# Mixer.net
KiCad netlist of a schematic drawn in Altium Designer
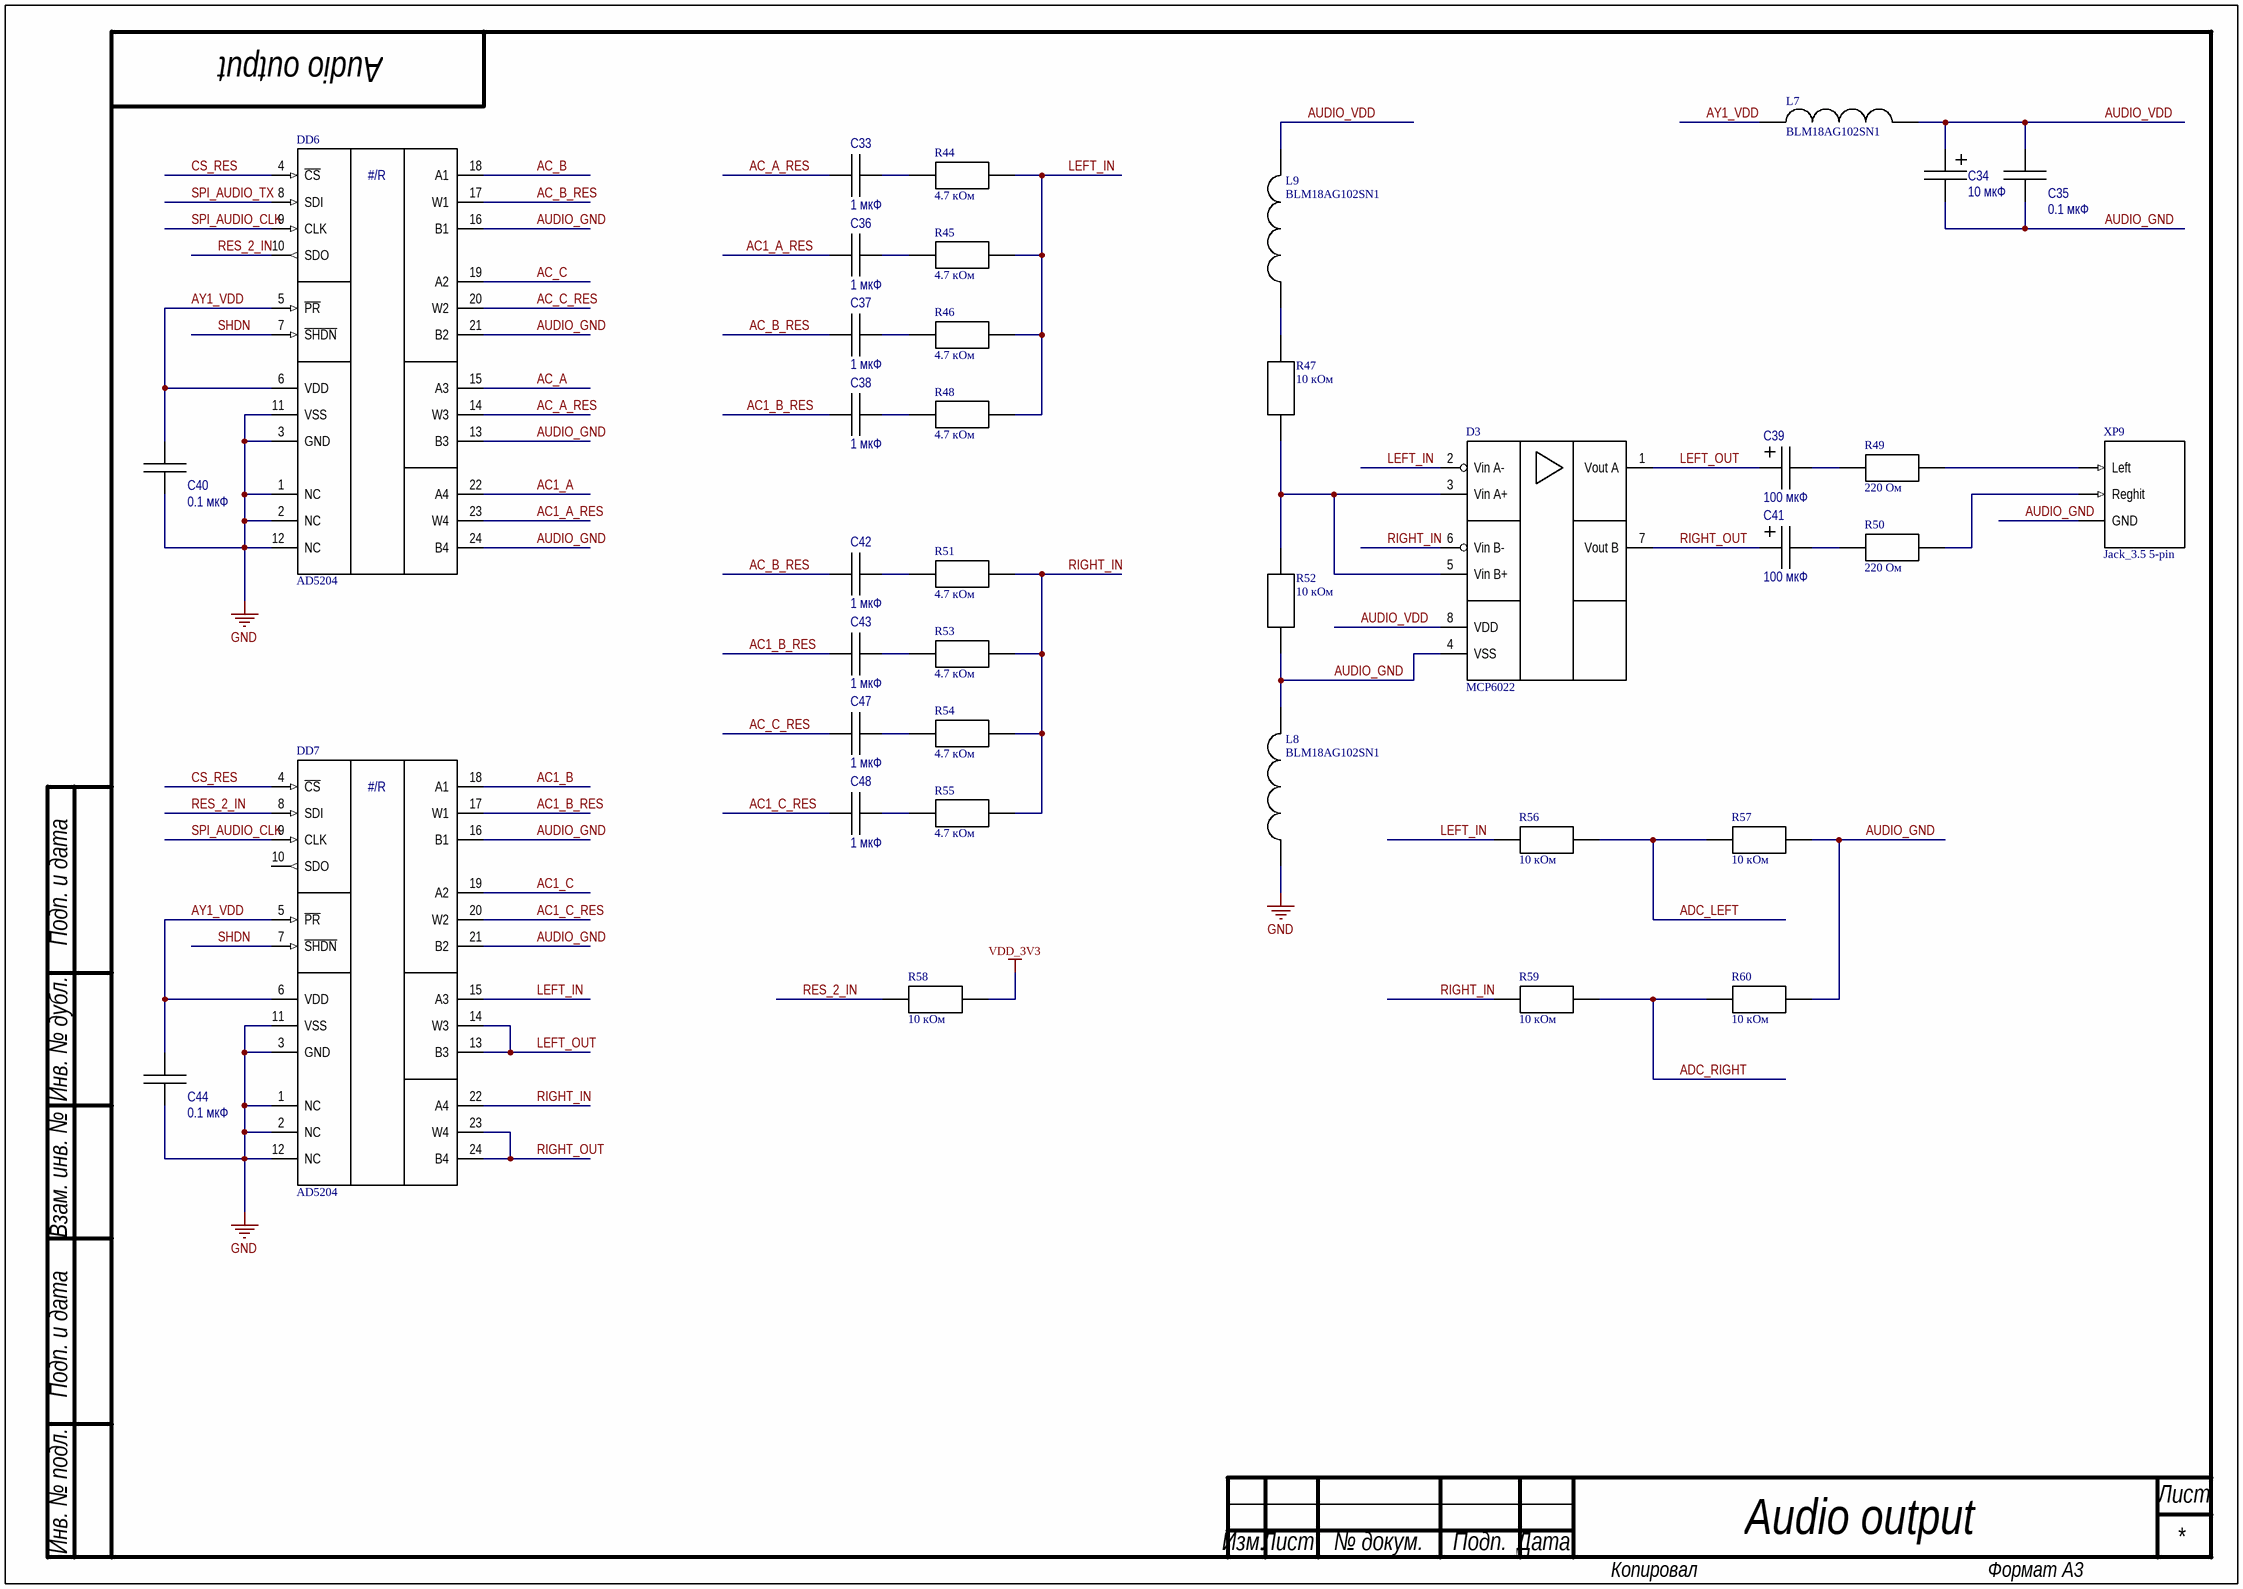
[diagram p0: Mixer.SchDoc]

(export (version "E")
  (design (tool "Eeschema 10.0.6"))
  (components
    (comp (ref "C33")
      (value "1 мкФ")
      (footprint "C 1206")
      (description "SMD Capacitor 1206")
      (fields
        (field (name "TOLERANCE") "/Укажите допуск в процентах/")
        (field (name "MANUFACTURER") "/Укажите компанию-производителя/")
      )
      (libsource (lib "my_lib") (part "CAP 1206"))
    )
    (comp (ref "C34")
      (value "10 мкФ")
      (footprint "C TAN_C")
      (description "SMD Tantalium Capacitor C")
      (fields
        (field (name "TOLERANCE") "/Укажите допуск в процентах/")
        (field (name "MANUFACTURER") "/Укажите компанию-производителя/")
      )
      (libsource (lib "my_lib") (part "CAP TAN_C"))
    )
    (comp (ref "C35")
      (value "0.1 мкФ")
      (footprint "C 1206")
      (description "SMD Capacitor 1206")
      (fields
        (field (name "TOLERANCE") "/Укажите допуск в процентах/")
        (field (name "MANUFACTURER") "/Укажите компанию-производителя/")
      )
      (libsource (lib "my_lib") (part "CAP 1206"))
    )
    (comp (ref "C36")
      (value "1 мкФ")
      (footprint "C 1206")
      (description "SMD Capacitor 1206")
      (fields
        (field (name "TOLERANCE") "/Укажите допуск в процентах/")
        (field (name "MANUFACTURER") "/Укажите компанию-производителя/")
      )
      (libsource (lib "my_lib") (part "CAP 1206"))
    )
    (comp (ref "C37")
      (value "1 мкФ")
      (footprint "C 1206")
      (description "SMD Capacitor 1206")
      (fields
        (field (name "TOLERANCE") "/Укажите допуск в процентах/")
        (field (name "MANUFACTURER") "/Укажите компанию-производителя/")
      )
      (libsource (lib "my_lib") (part "CAP 1206"))
    )
    (comp (ref "C38")
      (value "1 мкФ")
      (footprint "C 1206")
      (description "SMD Capacitor 1206")
      (fields
        (field (name "TOLERANCE") "/Укажите допуск в процентах/")
        (field (name "MANUFACTURER") "/Укажите компанию-производителя/")
      )
      (libsource (lib "my_lib") (part "CAP 1206"))
    )
    (comp (ref "C39")
      (value "100 мкФ")
      (footprint "C TAN_D")
      (description "SMD Tantalium Capacitor D")
      (fields
        (field (name "TOLERANCE") "/Укажите допуск в процентах/")
        (field (name "MANUFACTURER") "/Укажите компанию-производителя/")
      )
      (libsource (lib "my_lib") (part "CAP TAN_D"))
    )
    (comp (ref "C40")
      (value "0.1 мкФ")
      (footprint "C 1206")
      (description "SMD Capacitor 1206")
      (fields
        (field (name "TOLERANCE") "/Укажите допуск в процентах/")
        (field (name "MANUFACTURER") "/Укажите компанию-производителя/")
      )
      (libsource (lib "my_lib") (part "CAP 1206"))
    )
    (comp (ref "C41")
      (value "100 мкФ")
      (footprint "C TAN_D")
      (description "SMD Tantalium Capacitor D")
      (fields
        (field (name "TOLERANCE") "/Укажите допуск в процентах/")
        (field (name "MANUFACTURER") "/Укажите компанию-производителя/")
      )
      (libsource (lib "my_lib") (part "CAP TAN_D"))
    )
    (comp (ref "C42")
      (value "1 мкФ")
      (footprint "C 1206")
      (description "SMD Capacitor 1206")
      (fields
        (field (name "TOLERANCE") "/Укажите допуск в процентах/")
        (field (name "MANUFACTURER") "/Укажите компанию-производителя/")
      )
      (libsource (lib "my_lib") (part "CAP 1206"))
    )
    (comp (ref "C43")
      (value "1 мкФ")
      (footprint "C 1206")
      (description "SMD Capacitor 1206")
      (fields
        (field (name "TOLERANCE") "/Укажите допуск в процентах/")
        (field (name "MANUFACTURER") "/Укажите компанию-производителя/")
      )
      (libsource (lib "my_lib") (part "CAP 1206"))
    )
    (comp (ref "C44")
      (value "0.1 мкФ")
      (footprint "C 1206")
      (description "SMD Capacitor 1206")
      (fields
        (field (name "TOLERANCE") "/Укажите допуск в процентах/")
        (field (name "MANUFACTURER") "/Укажите компанию-производителя/")
      )
      (libsource (lib "my_lib") (part "CAP 1206"))
    )
    (comp (ref "C47")
      (value "1 мкФ")
      (footprint "C 1206")
      (description "SMD Capacitor 1206")
      (fields
        (field (name "TOLERANCE") "/Укажите допуск в процентах/")
        (field (name "MANUFACTURER") "/Укажите компанию-производителя/")
      )
      (libsource (lib "my_lib") (part "CAP 1206"))
    )
    (comp (ref "C48")
      (value "1 мкФ")
      (footprint "C 1206")
      (description "SMD Capacitor 1206")
      (fields
        (field (name "TOLERANCE") "/Укажите допуск в процентах/")
        (field (name "MANUFACTURER") "/Укажите компанию-производителя/")
      )
      (libsource (lib "my_lib") (part "CAP 1206"))
    )
    (comp (ref "D3") (value "MCP6022") (footprint "SOIC-8") (libsource (lib "my_lib") (part "MCP6022")))
    (comp (ref "DD6") (value "AD5204") (footprint "TSSOP-24") (libsource (lib "my_lib") (part "AD5204")))
    (comp (ref "DD7") (value "AD5204") (footprint "TSSOP-24") (libsource (lib "my_lib") (part "AD5204")))
    (comp (ref "L7")
      (value "BLM18AG102SN1")
      (footprint "FB 0603")
      (libsource (lib "my_lib") (part "BLM18AG102SN1"))
    )
    (comp (ref "L8")
      (value "BLM18AG102SN1")
      (footprint "FB 0603")
      (libsource (lib "my_lib") (part "BLM18AG102SN1"))
    )
    (comp (ref "L9")
      (value "BLM18AG102SN1")
      (footprint "FB 0603")
      (libsource (lib "my_lib") (part "BLM18AG102SN1"))
    )
    (comp (ref "R44") (value "4.7 кОм") (footprint "RES 0805") (libsource (lib "my_lib") (part "RES 0805")))
    (comp (ref "R45") (value "4.7 кОм") (footprint "RES 0805") (libsource (lib "my_lib") (part "RES 0805")))
    (comp (ref "R46") (value "4.7 кОм") (footprint "RES 0805") (libsource (lib "my_lib") (part "RES 0805")))
    (comp (ref "R47") (value "10 кОм") (footprint "RES 0805") (libsource (lib "my_lib") (part "RES 0805")))
    (comp (ref "R48") (value "4.7 кОм") (footprint "RES 0805") (libsource (lib "my_lib") (part "RES 0805")))
    (comp (ref "R49") (value "220 Ом") (footprint "RES 0805") (libsource (lib "my_lib") (part "RES 0805")))
    (comp (ref "R50") (value "220 Ом") (footprint "RES 0805") (libsource (lib "my_lib") (part "RES 0805")))
    (comp (ref "R51") (value "4.7 кОм") (footprint "RES 0805") (libsource (lib "my_lib") (part "RES 0805")))
    (comp (ref "R52") (value "10 кОм") (footprint "RES 0805") (libsource (lib "my_lib") (part "RES 0805")))
    (comp (ref "R53") (value "4.7 кОм") (footprint "RES 0805") (libsource (lib "my_lib") (part "RES 0805")))
    (comp (ref "R54") (value "4.7 кОм") (footprint "RES 0805") (libsource (lib "my_lib") (part "RES 0805")))
    (comp (ref "R55") (value "4.7 кОм") (footprint "RES 0805") (libsource (lib "my_lib") (part "RES 0805")))
    (comp (ref "R56") (value "10 кОм") (footprint "RES 0805") (libsource (lib "my_lib") (part "RES 0805")))
    (comp (ref "R57") (value "10 кОм") (footprint "RES 0805") (libsource (lib "my_lib") (part "RES 0805")))
    (comp (ref "R58") (value "10 кОм") (footprint "RES 0805") (libsource (lib "my_lib") (part "RES 0805")))
    (comp (ref "R59") (value "10 кОм") (footprint "RES 0805") (libsource (lib "my_lib") (part "RES 0805")))
    (comp (ref "R60") (value "10 кОм") (footprint "RES 0805") (libsource (lib "my_lib") (part "RES 0805")))
    (comp (ref "XP9")
      (value "Jack_3.5 5-pin")
      (footprint "JACK 3.5  female")
      (libsource (lib "my_lib") (part "Jack_3.5 5-pin"))
    )
  )
  (nets
    (net (code "1") (name "/AC1_A") (class "Default")
      (node (ref "DD6") (pin "22") (pinfunction "A4_22") (pintype "passive"))
    )
    (net (code "2") (name "/AC1_A_RES") (class "Default")
      (node (ref "C36") (pin "1") (pinfunction "1_1") (pintype "passive"))
      (node (ref "DD6") (pin "23") (pinfunction "W4_23") (pintype "passive"))
    )
    (net (code "3") (name "/AC1_B") (class "Default")
      (node (ref "DD7") (pin "18") (pinfunction "A1_18") (pintype "passive"))
    )
    (net (code "4") (name "/AC1_B_RES") (class "Default")
      (node (ref "C38") (pin "1") (pinfunction "1_1") (pintype "passive"))
      (node (ref "C43") (pin "1") (pinfunction "1_1") (pintype "passive"))
      (node (ref "DD7") (pin "17") (pinfunction "W1_17") (pintype "passive"))
    )
    (net (code "5") (name "/AC1_C") (class "Default")
      (node (ref "DD7") (pin "19") (pinfunction "A2_19") (pintype "passive"))
    )
    (net (code "6") (name "/AC1_C_RES") (class "Default")
      (node (ref "C48") (pin "1") (pinfunction "1_1") (pintype "passive"))
      (node (ref "DD7") (pin "20") (pinfunction "W2_20") (pintype "passive"))
    )
    (net (code "7") (name "/AC_A") (class "Default")
      (node (ref "DD6") (pin "15") (pinfunction "A3_15") (pintype "passive"))
    )
    (net (code "8") (name "/AC_A_RES") (class "Default")
      (node (ref "C33") (pin "1") (pinfunction "1_1") (pintype "passive"))
      (node (ref "DD6") (pin "14") (pinfunction "W3_14") (pintype "passive"))
    )
    (net (code "9") (name "/AC_B") (class "Default")
      (node (ref "DD6") (pin "18") (pinfunction "A1_18") (pintype "passive"))
    )
    (net (code "10") (name "/AC_B_RES") (class "Default")
      (node (ref "C37") (pin "1") (pinfunction "1_1") (pintype "passive"))
      (node (ref "C42") (pin "1") (pinfunction "1_1") (pintype "passive"))
      (node (ref "DD6") (pin "17") (pinfunction "W1_17") (pintype "passive"))
    )
    (net (code "11") (name "/AC_C") (class "Default")
      (node (ref "DD6") (pin "19") (pinfunction "A2_19") (pintype "passive"))
    )
    (net (code "12") (name "/AC_C_RES") (class "Default")
      (node (ref "C47") (pin "1") (pinfunction "1_1") (pintype "passive"))
      (node (ref "DD6") (pin "20") (pinfunction "W2_20") (pintype "passive"))
    )
    (net (code "13") (name "/ADC_LEFT") (class "Default")
      (node (ref "R56") (pin "1") (pinfunction "1_1") (pintype "passive"))
      (node (ref "R57") (pin "2") (pinfunction "2_2") (pintype "passive"))
    )
    (net (code "14") (name "/ADC_RIGHT") (class "Default")
      (node (ref "R59") (pin "1") (pinfunction "1_1") (pintype "passive"))
      (node (ref "R60") (pin "2") (pinfunction "2_2") (pintype "passive"))
    )
    (net (code "15") (name "/AUDIO_GND") (class "Default")
      (node (ref "C34") (pin "2") (pinfunction "2_2") (pintype "passive"))
      (node (ref "C35") (pin "2") (pinfunction "2_2") (pintype "passive"))
      (node (ref "D3") (pin "4") (pinfunction "VSS_4") (pintype "power_in"))
      (node (ref "DD6") (pin "13") (pinfunction "B3_13") (pintype "passive"))
      (node (ref "DD6") (pin "16") (pinfunction "B1_16") (pintype "passive"))
      (node (ref "DD6") (pin "21") (pinfunction "B2_21") (pintype "passive"))
      (node (ref "DD6") (pin "24") (pinfunction "B4_24") (pintype "passive"))
      (node (ref "DD7") (pin "16") (pinfunction "B1_16") (pintype "passive"))
      (node (ref "DD7") (pin "21") (pinfunction "B2_21") (pintype "passive"))
      (node (ref "L8") (pin "2") (pinfunction "2_2") (pintype "passive"))
      (node (ref "R52") (pin "1") (pinfunction "1_1") (pintype "passive"))
      (node (ref "R57") (pin "1") (pinfunction "1_1") (pintype "passive"))
      (node (ref "R60") (pin "1") (pinfunction "1_1") (pintype "passive"))
      (node (ref "XP9") (pin "G") (pinfunction "GND_G") (pintype "power_in"))
    )
    (net (code "16") (name "/AUDIO_VDD") (class "Default")
      (node (ref "C34") (pin "1") (pinfunction "1_1") (pintype "passive"))
      (node (ref "C35") (pin "1") (pinfunction "1_1") (pintype "passive"))
      (node (ref "D3") (pin "8") (pinfunction "VDD_8") (pintype "power_in"))
      (node (ref "L7") (pin "2") (pinfunction "2_2") (pintype "passive"))
      (node (ref "L9") (pin "2") (pinfunction "2_2") (pintype "passive"))
    )
    (net (code "17") (name "/AY1_VDD") (class "Default")
      (node (ref "C40") (pin "1") (pinfunction "1_1") (pintype "passive"))
      (node (ref "C44") (pin "1") (pinfunction "1_1") (pintype "passive"))
      (node (ref "DD6") (pin "5") (pinfunction "~{PR}_5") (pintype "input"))
      (node (ref "DD6") (pin "6") (pinfunction "VDD_6") (pintype "power_in"))
      (node (ref "DD7") (pin "5") (pinfunction "~{PR}_5") (pintype "input"))
      (node (ref "DD7") (pin "6") (pinfunction "VDD_6") (pintype "power_in"))
      (node (ref "L7") (pin "1") (pinfunction "1_1") (pintype "passive"))
    )
    (net (code "18") (name "/CS_RES") (class "Default")
      (node (ref "DD6") (pin "4") (pinfunction "~{CS}_4") (pintype "input"))
      (node (ref "DD7") (pin "4") (pinfunction "~{CS}_4") (pintype "input"))
    )
    (net (code "19") (name "/LEFT_IN") (class "Default")
      (node (ref "D3") (pin "2") (pinfunction "Vin_A-_2") (pintype "passive"))
      (node (ref "DD7") (pin "15") (pinfunction "A3_15") (pintype "passive"))
      (node (ref "R44") (pin "2") (pinfunction "2_2") (pintype "passive"))
      (node (ref "R45") (pin "2") (pinfunction "2_2") (pintype "passive"))
      (node (ref "R46") (pin "2") (pinfunction "2_2") (pintype "passive"))
      (node (ref "R48") (pin "2") (pinfunction "2_2") (pintype "passive"))
      (node (ref "R56") (pin "2") (pinfunction "2_2") (pintype "passive"))
    )
    (net (code "20") (name "/LEFT_OUT") (class "Default")
      (node (ref "C39") (pin "1") (pinfunction "1_1") (pintype "passive"))
      (node (ref "D3") (pin "1") (pinfunction "Vout_A_1") (pintype "passive"))
      (node (ref "DD7") (pin "13") (pinfunction "B3_13") (pintype "passive"))
      (node (ref "DD7") (pin "14") (pinfunction "W3_14") (pintype "passive"))
    )
    (net (code "21") (name "/RES_2_IN") (class "Default")
      (node (ref "DD6") (pin "10") (pinfunction "SDO_10") (pintype "output"))
      (node (ref "DD7") (pin "8") (pinfunction "SDI_8") (pintype "input"))
      (node (ref "R58") (pin "1") (pinfunction "1_1") (pintype "passive"))
    )
    (net (code "22") (name "/RIGHT_IN") (class "Default")
      (node (ref "D3") (pin "6") (pinfunction "Vin_B-_6") (pintype "passive"))
      (node (ref "DD7") (pin "22") (pinfunction "A4_22") (pintype "passive"))
      (node (ref "R51") (pin "2") (pinfunction "2_2") (pintype "passive"))
      (node (ref "R53") (pin "2") (pinfunction "2_2") (pintype "passive"))
      (node (ref "R54") (pin "2") (pinfunction "2_2") (pintype "passive"))
      (node (ref "R55") (pin "2") (pinfunction "2_2") (pintype "passive"))
      (node (ref "R59") (pin "2") (pinfunction "2_2") (pintype "passive"))
    )
    (net (code "23") (name "/RIGHT_OUT") (class "Default")
      (node (ref "C41") (pin "1") (pinfunction "1_1") (pintype "passive"))
      (node (ref "D3") (pin "7") (pinfunction "Vout_B_7") (pintype "passive"))
      (node (ref "DD7") (pin "23") (pinfunction "W4_23") (pintype "passive"))
      (node (ref "DD7") (pin "24") (pinfunction "B4_24") (pintype "passive"))
    )
    (net (code "24") (name "/SHDN") (class "Default")
      (node (ref "DD6") (pin "7") (pinfunction "~{SHDN}_7") (pintype "input"))
      (node (ref "DD7") (pin "7") (pinfunction "~{SHDN}_7") (pintype "input"))
    )
    (net (code "25") (name "/SPI_AUDIO_CLK") (class "Default")
      (node (ref "DD6") (pin "9") (pinfunction "CLK_9") (pintype "input"))
      (node (ref "DD7") (pin "9") (pinfunction "CLK_9") (pintype "input"))
    )
    (net (code "26") (name "/SPI_AUDIO_TX") (class "Default")
      (node (ref "DD6") (pin "8") (pinfunction "SDI_8") (pintype "input"))
    )
    (net (code "27") (name "GND") (class "Default")
      (node (ref "C40") (pin "2") (pinfunction "2_2") (pintype "passive"))
      (node (ref "C44") (pin "2") (pinfunction "2_2") (pintype "passive"))
      (node (ref "DD6") (pin "1") (pinfunction "NC_1") (pintype "passive"))
      (node (ref "DD6") (pin "11") (pinfunction "VSS_11") (pintype "power_in"))
      (node (ref "DD6") (pin "12") (pinfunction "NC_12") (pintype "passive"))
      (node (ref "DD6") (pin "2") (pinfunction "NC_2") (pintype "passive"))
      (node (ref "DD6") (pin "3") (pinfunction "GND_3") (pintype "power_in"))
      (node (ref "DD7") (pin "1") (pinfunction "NC_1") (pintype "passive"))
      (node (ref "DD7") (pin "11") (pinfunction "VSS_11") (pintype "power_in"))
      (node (ref "DD7") (pin "12") (pinfunction "NC_12") (pintype "passive"))
      (node (ref "DD7") (pin "2") (pinfunction "NC_2") (pintype "passive"))
      (node (ref "DD7") (pin "3") (pinfunction "GND_3") (pintype "power_in"))
      (node (ref "L8") (pin "1") (pinfunction "1_1") (pintype "passive"))
    )
    (net (code "28") (name "Net-(C33-Pad2)") (class "Default")
      (node (ref "C33") (pin "2") (pinfunction "2_2") (pintype "passive"))
      (node (ref "R44") (pin "1") (pinfunction "1_1") (pintype "passive"))
    )
    (net (code "29") (name "Net-(C36-Pad2)") (class "Default")
      (node (ref "C36") (pin "2") (pinfunction "2_2") (pintype "passive"))
      (node (ref "R45") (pin "1") (pinfunction "1_1") (pintype "passive"))
    )
    (net (code "30") (name "Net-(C37-Pad2)") (class "Default")
      (node (ref "C37") (pin "2") (pinfunction "2_2") (pintype "passive"))
      (node (ref "R46") (pin "1") (pinfunction "1_1") (pintype "passive"))
    )
    (net (code "31") (name "Net-(C38-Pad2)") (class "Default")
      (node (ref "C38") (pin "2") (pinfunction "2_2") (pintype "passive"))
      (node (ref "R48") (pin "1") (pinfunction "1_1") (pintype "passive"))
    )
    (net (code "32") (name "Net-(C39-Pad2)") (class "Default")
      (node (ref "C39") (pin "2") (pinfunction "2_2") (pintype "passive"))
      (node (ref "R49") (pin "1") (pinfunction "1_1") (pintype "passive"))
    )
    (net (code "33") (name "Net-(C41-Pad2)") (class "Default")
      (node (ref "C41") (pin "2") (pinfunction "2_2") (pintype "passive"))
      (node (ref "R50") (pin "1") (pinfunction "1_1") (pintype "passive"))
    )
    (net (code "34") (name "Net-(C42-Pad2)") (class "Default")
      (node (ref "C42") (pin "2") (pinfunction "2_2") (pintype "passive"))
      (node (ref "R51") (pin "1") (pinfunction "1_1") (pintype "passive"))
    )
    (net (code "35") (name "Net-(C43-Pad2)") (class "Default")
      (node (ref "C43") (pin "2") (pinfunction "2_2") (pintype "passive"))
      (node (ref "R53") (pin "1") (pinfunction "1_1") (pintype "passive"))
    )
    (net (code "36") (name "Net-(C47-Pad2)") (class "Default")
      (node (ref "C47") (pin "2") (pinfunction "2_2") (pintype "passive"))
      (node (ref "R54") (pin "1") (pinfunction "1_1") (pintype "passive"))
    )
    (net (code "37") (name "Net-(C48-Pad2)") (class "Default")
      (node (ref "C48") (pin "2") (pinfunction "2_2") (pintype "passive"))
      (node (ref "R55") (pin "1") (pinfunction "1_1") (pintype "passive"))
    )
    (net (code "38") (name "Net-(D3-Vin_A+)") (class "Default")
      (node (ref "D3") (pin "3") (pinfunction "Vin_A+_3") (pintype "passive"))
      (node (ref "D3") (pin "5") (pinfunction "Vin_B+_5") (pintype "passive"))
      (node (ref "R47") (pin "1") (pinfunction "1_1") (pintype "passive"))
      (node (ref "R52") (pin "2") (pinfunction "2_2") (pintype "passive"))
    )
    (net (code "39") (name "Net-(L9-Pad1)") (class "Default")
      (node (ref "L9") (pin "1") (pinfunction "1_1") (pintype "passive"))
      (node (ref "R47") (pin "2") (pinfunction "2_2") (pintype "passive"))
    )
    (net (code "40") (name "Net-(XP9-Left)") (class "Default")
      (node (ref "R49") (pin "2") (pinfunction "2_2") (pintype "passive"))
      (node (ref "XP9") (pin "L") (pinfunction "Left_L") (pintype "input"))
    )
    (net (code "41") (name "Net-(XP9-Reghit)") (class "Default")
      (node (ref "R50") (pin "2") (pinfunction "2_2") (pintype "passive"))
      (node (ref "XP9") (pin "R") (pinfunction "Reghit_R") (pintype "input"))
    )
    (net (code "42") (name "VDD_3V3") (class "Default")
      (node (ref "R58") (pin "2") (pinfunction "2_2") (pintype "passive"))
    )
    (net (code "43") (name "unconnected-(DD7-SDO-Pad10)") (class "Default")
      (node (ref "DD7") (pin "10") (pinfunction "SDO_10") (pintype "output"))
    )
  )
)
